# CurrentSense.net
KiCad netlist of a schematic drawn in Altium Designer
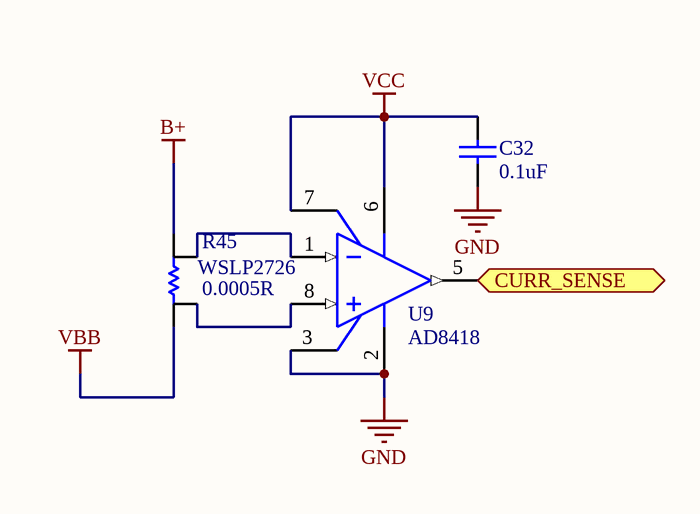
[diagram p0: CurrentSense.SchDoc]

(export (version "E")
  (design (tool "Eeschema 10.0.6"))
  (components
    (comp (ref "C32")
      (value "0.1uF")
      (footprint "C0402[1005X55]")
      (description "0.1uF 6.3V 10% 0402 (1005 Metric)")
      (fields (field (name "TOLERANCE") "10%") (field (name "PARTNUMBER") "GRM155R70J104KA01D"))
      (libsource (lib "Capacitors") (part "CAP_0.1uF_6.3V_0402_10%"))
    )
    (comp (ref "R45")
      (value "WSLP2726")
      (footprint "WSL2726")
      (description "Resistor")
      (fields (field (name "ALTIUM_VALUE") "0.0005R") (field (name "PUBLISHER") "Altium Limited"))
      (libsource (lib "Components") (part "WSLP2726"))
    )
    (comp (ref "U9") (value "AD8418") (footprint "MSOP-8") (libsource (lib "Components") (part "AD8418")))
  )
  (nets
    (net (code "1") (name "/CURR_SENSE") (class "Default")
      (node (ref "U9") (pin "5") (pinfunction "OUT_5") (pintype "output"))
    )
    (net (code "2") (name "B+") (class "Default")
      (node (ref "R45") (pin "2") (pinfunction "2_2") (pintype "passive"))
    )
    (net (code "3") (name "GND") (class "Default")
      (node (ref "C32") (pin "1") (pinfunction "1_1") (pintype "passive"))
      (node (ref "U9") (pin "2") (pinfunction "GND_2") (pintype "power_in"))
      (node (ref "U9") (pin "3") (pinfunction "VREF2_3") (pintype "passive"))
    )
    (net (code "4") (name "Net-(U9-IN+)") (class "Default")
      (node (ref "R45") (pin "3") (pinfunction "3_3") (pintype "passive"))
      (node (ref "U9") (pin "8") (pinfunction "IN+_8") (pintype "input"))
    )
    (net (code "5") (name "Net-(U9-IN-)") (class "Default")
      (node (ref "R45") (pin "4") (pinfunction "4_4") (pintype "passive"))
      (node (ref "U9") (pin "1") (pinfunction "IN-_1") (pintype "input"))
    )
    (net (code "6") (name "VBB") (class "Default")
      (node (ref "R45") (pin "1") (pinfunction "1_1") (pintype "passive"))
    )
    (net (code "7") (name "VCC") (class "Default")
      (node (ref "C32") (pin "2") (pinfunction "2_2") (pintype "passive"))
      (node (ref "U9") (pin "6") (pinfunction "VS_6") (pintype "power_in"))
      (node (ref "U9") (pin "7") (pinfunction "VREF1_7") (pintype "passive"))
    )
  )
)
